# Cree_XP-E_Turn.net
KiCad netlist of a schematic drawn in EAGLE
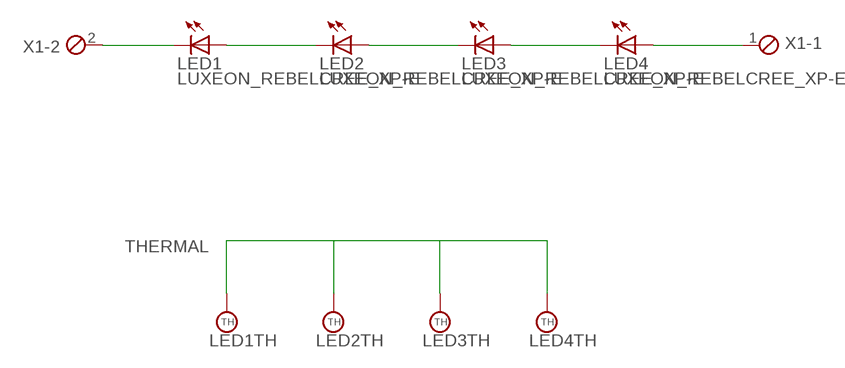
[diagram p0: schematic, sheet 1]

(export (version "E")
  (design (tool "Eeschema 10.0.6"))
  (components
    (comp (ref "LED1")
      (value "LUXEON_REBELCREE_XP-E")
      (footprint "eagle-import:CREE_XP-E")
      (libsource (lib "eagle-import") (part "LUXEON_REBELCREE_XP-E"))
    )
    (comp (ref "LED2")
      (value "LUXEON_REBELCREE_XP-E")
      (footprint "eagle-import:CREE_XP-E")
      (libsource (lib "eagle-import") (part "LUXEON_REBELCREE_XP-E"))
    )
    (comp (ref "LED3")
      (value "LUXEON_REBELCREE_XP-E")
      (footprint "eagle-import:CREE_XP-E")
      (libsource (lib "eagle-import") (part "LUXEON_REBELCREE_XP-E"))
    )
    (comp (ref "LED4")
      (value "LUXEON_REBELCREE_XP-E")
      (footprint "eagle-import:CREE_XP-E")
      (libsource (lib "eagle-import") (part "LUXEON_REBELCREE_XP-E"))
    )
    (comp (ref "X1")
      (value "MPT2")
      (footprint "eagle-import:2POL254")
      (libsource (lib "eagle-import") (part "MPT2"))
    )
  )
  (nets
    (net (code "1") (name "/THERMAL") (class "Default")
      (node (ref "LED1") (pin "TH") (pinfunction "TH_TH") (pintype "passive"))
      (node (ref "LED2") (pin "TH") (pinfunction "TH_TH") (pintype "passive"))
      (node (ref "LED3") (pin "TH") (pinfunction "TH_TH") (pintype "passive"))
      (node (ref "LED4") (pin "TH") (pinfunction "TH_TH") (pintype "passive"))
    )
    (net (code "2") (name "Net-(LED1A-A)") (class "Default")
      (node (ref "LED1") (pin "AN") (pinfunction "A_AN") (pintype "passive"))
      (node (ref "LED2") (pin "CT") (pinfunction "C_CT") (pintype "passive"))
    )
    (net (code "3") (name "Net-(LED1A-C)") (class "Default")
      (node (ref "LED1") (pin "CT") (pinfunction "C_CT") (pintype "passive"))
      (node (ref "X1") (pin "2") (pinfunction "1_2") (pintype "passive"))
    )
    (net (code "4") (name "Net-(LED2A-A)") (class "Default")
      (node (ref "LED2") (pin "AN") (pinfunction "A_AN") (pintype "passive"))
      (node (ref "LED3") (pin "CT") (pinfunction "C_CT") (pintype "passive"))
    )
    (net (code "5") (name "Net-(LED3A-A)") (class "Default")
      (node (ref "LED3") (pin "AN") (pinfunction "A_AN") (pintype "passive"))
      (node (ref "LED4") (pin "CT") (pinfunction "C_CT") (pintype "passive"))
    )
    (net (code "6") (name "Net-(LED4A-A)") (class "Default")
      (node (ref "LED4") (pin "AN") (pinfunction "A_AN") (pintype "passive"))
      (node (ref "X1") (pin "1") (pinfunction "1_1") (pintype "passive"))
    )
  )
)
